# spice-usbc.net
KiCad netlist of a schematic drawn in EAGLE
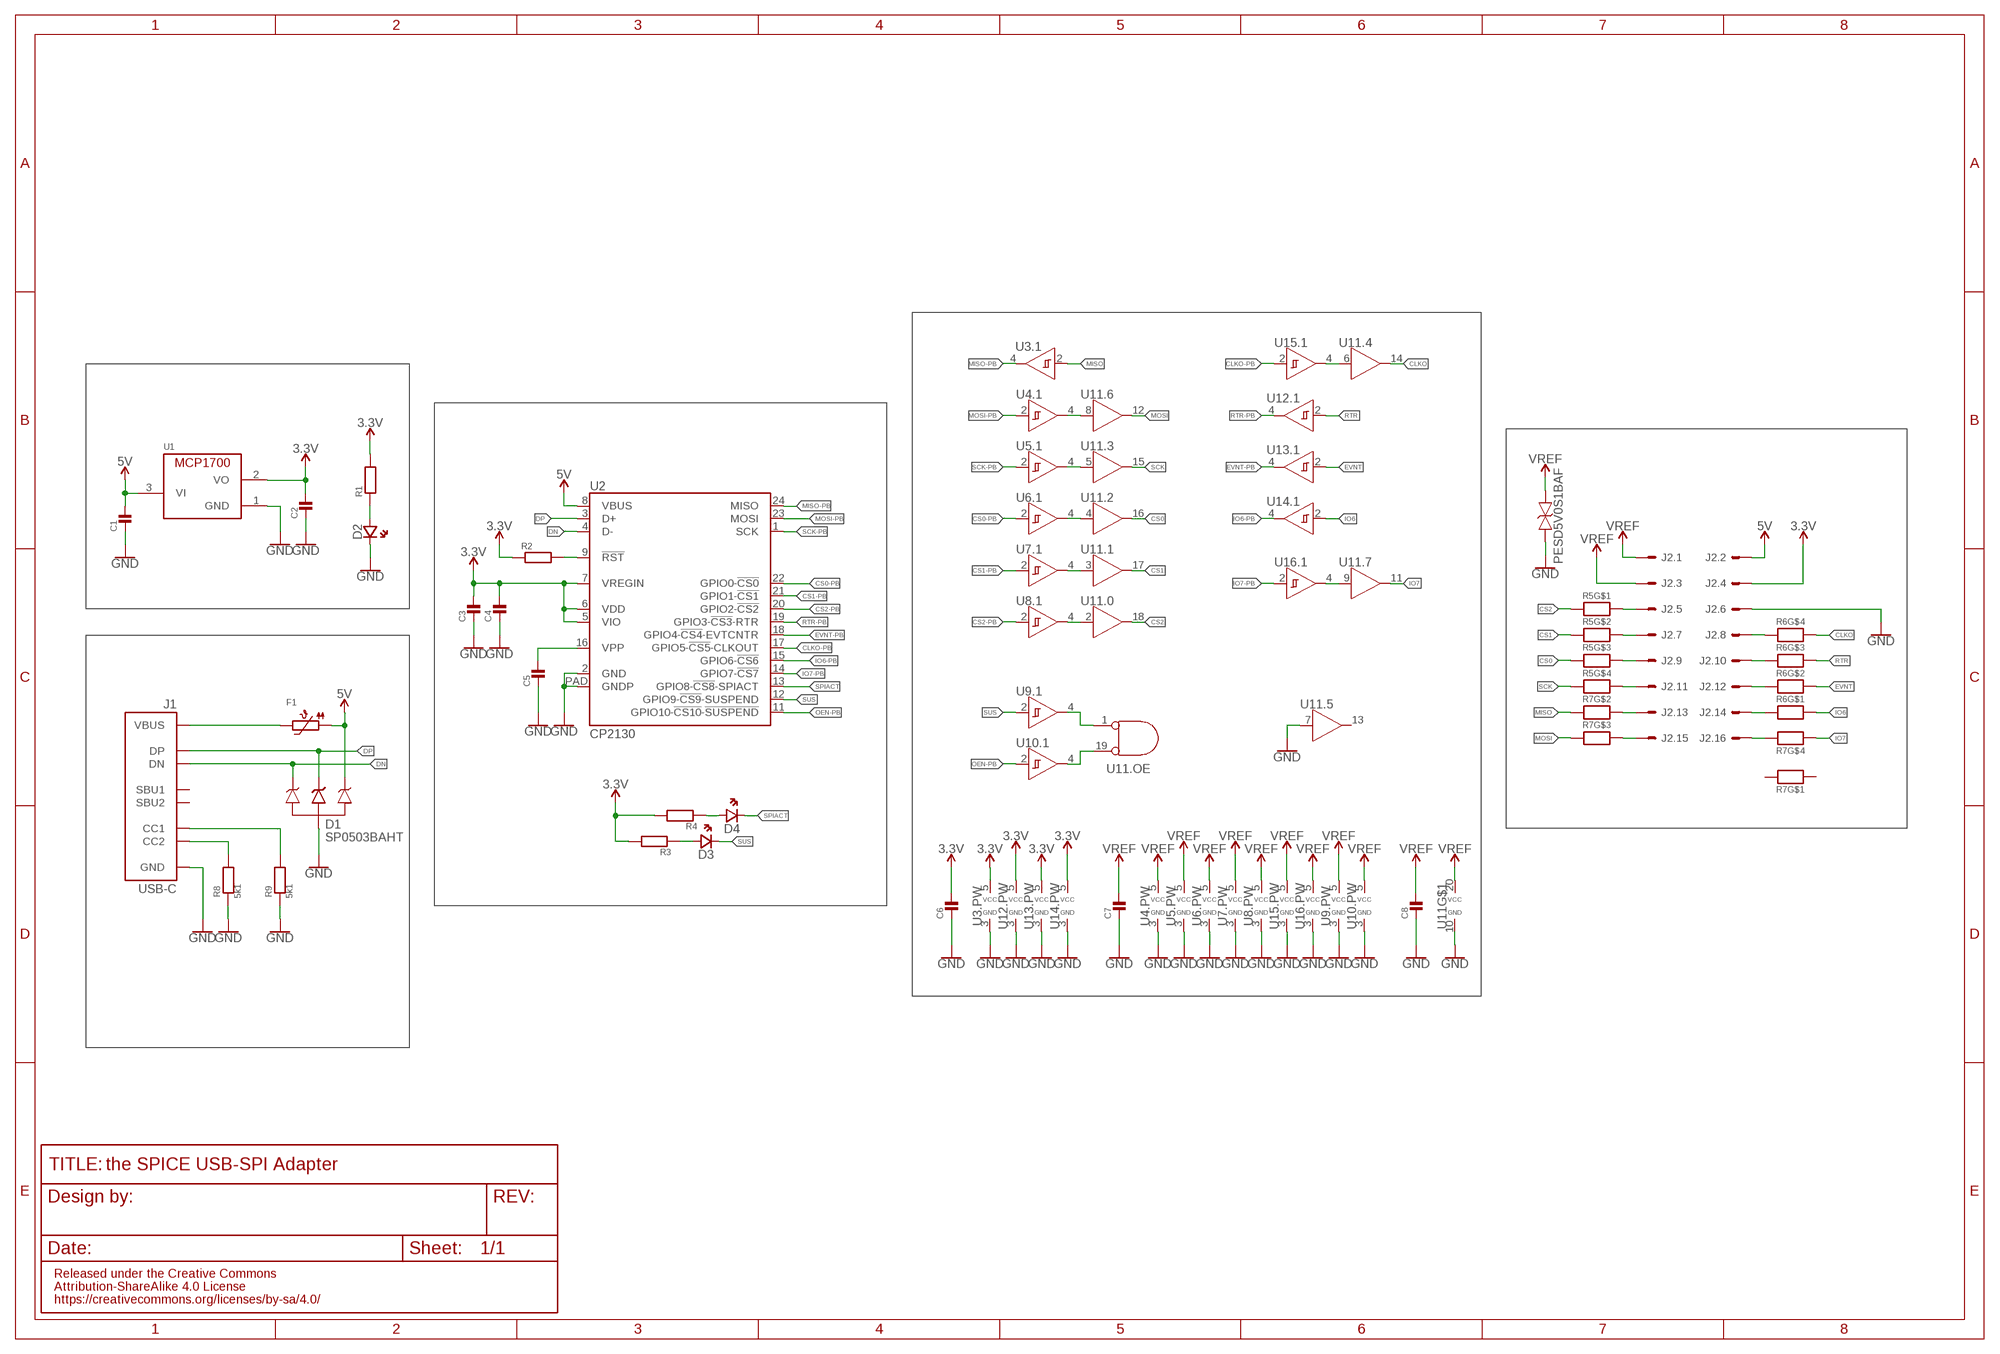
[diagram p0: schematic, sheet 1]

(export (version "E")
  (design (tool "Eeschema 10.0.6"))
  (components
    (comp (ref "C1")
      (value "MLCC0603")
      (footprint "eagle-import:0603_WAVE")
      (libsource (lib "eagle-import") (part "MLCC0603"))
    )
    (comp (ref "C2")
      (value "MLCC0603")
      (footprint "eagle-import:0603_WAVE")
      (libsource (lib "eagle-import") (part "MLCC0603"))
    )
    (comp (ref "C3")
      (value "MLCC0603")
      (footprint "eagle-import:0603_WAVE")
      (libsource (lib "eagle-import") (part "MLCC0603"))
    )
    (comp (ref "C4")
      (value "MLCC0603")
      (footprint "eagle-import:0603_WAVE")
      (libsource (lib "eagle-import") (part "MLCC0603"))
    )
    (comp (ref "C5")
      (value "MLCC0603")
      (footprint "eagle-import:0603_WAVE")
      (libsource (lib "eagle-import") (part "MLCC0603"))
    )
    (comp (ref "C6")
      (value "MLCC0603")
      (footprint "eagle-import:0603_WAVE")
      (libsource (lib "eagle-import") (part "MLCC0603"))
    )
    (comp (ref "C7")
      (value "MLCC0603")
      (footprint "eagle-import:0603_WAVE")
      (libsource (lib "eagle-import") (part "MLCC0603"))
    )
    (comp (ref "C8")
      (value "MLCC0603")
      (footprint "eagle-import:0603_WAVE")
      (libsource (lib "eagle-import") (part "MLCC0603"))
    )
    (comp (ref "D1")
      (value "SP0503BAHT")
      (footprint "eagle-import:SOT143")
      (libsource (lib "eagle-import") (part "SP0503BAHT"))
    )
    (comp (ref "D2")
      (value "LED0603")
      (footprint "eagle-import:CHIPLED_0603")
      (libsource (lib "eagle-import") (part "LED0603"))
    )
    (comp (ref "D3")
      (value "LED0603")
      (footprint "eagle-import:CHIPLED_0603")
      (libsource (lib "eagle-import") (part "LED0603"))
    )
    (comp (ref "D4")
      (value "LED0603")
      (footprint "eagle-import:CHIPLED_0603")
      (libsource (lib "eagle-import") (part "LED0603"))
    )
    (comp (ref "D5")
      (value "PESD5V0S1BAF")
      (footprint "eagle-import:SOD323")
      (libsource (lib "eagle-import") (part "PESD5V0S1BAF"))
    )
    (comp (ref "F1")
      (value "PTC1210")
      (footprint "eagle-import:PTC1210")
      (libsource (lib "eagle-import") (part "PTC1210"))
    )
    (comp (ref "J1")
      (value "USB-C")
      (footprint "eagle-import:USB-C")
      (libsource (lib "eagle-import") (part "USB-C"))
    )
    (comp (ref "J2")
      (value "2X8")
      (footprint "eagle-import:2X8_2.54")
      (libsource (lib "eagle-import") (part "2X8"))
    )
    (comp (ref "R1")
      (value "RESISTOR0603")
      (footprint "eagle-import:0603_WAVE")
      (libsource (lib "eagle-import") (part "RESISTOR0603"))
    )
    (comp (ref "R2")
      (value "RESISTOR0603")
      (footprint "eagle-import:0603_WAVE")
      (libsource (lib "eagle-import") (part "RESISTOR0603"))
    )
    (comp (ref "R3")
      (value "RESISTOR0603")
      (footprint "eagle-import:0603_WAVE")
      (libsource (lib "eagle-import") (part "RESISTOR0603"))
    )
    (comp (ref "R4")
      (value "RESISTOR0603")
      (footprint "eagle-import:0603_WAVE")
      (libsource (lib "eagle-import") (part "RESISTOR0603"))
    )
    (comp (ref "R5")
      (value "RESISTOR_4PACK")
      (footprint "eagle-import:RESPACK_4X0603")
      (libsource (lib "eagle-import") (part "RESISTOR_4PACK"))
    )
    (comp (ref "R6")
      (value "RESISTOR_4PACK")
      (footprint "eagle-import:RESPACK_4X0603")
      (libsource (lib "eagle-import") (part "RESISTOR_4PACK"))
    )
    (comp (ref "R7")
      (value "RESISTOR_4PACK")
      (footprint "eagle-import:RESPACK_4X0603")
      (libsource (lib "eagle-import") (part "RESISTOR_4PACK"))
    )
    (comp (ref "R8")
      (value "5k1")
      (footprint "eagle-import:0603_WAVE")
      (libsource (lib "eagle-import") (part "RESISTOR0603"))
    )
    (comp (ref "R9")
      (value "5k1")
      (footprint "eagle-import:0603_WAVE")
      (libsource (lib "eagle-import") (part "RESISTOR0603"))
    )
    (comp (ref "U1")
      (value "MCP1700T-3302TT")
      (footprint "eagle-import:SOT-23")
      (libsource (lib "eagle-import") (part "MCP1700T-3302TT"))
    )
    (comp (ref "U2")
      (value "CP2130")
      (footprint "eagle-import:QFN24")
      (libsource (lib "eagle-import") (part "CP2130"))
    )
    (comp (ref "U3")
      (value "74LVC1G17")
      (footprint "eagle-import:SC70-5")
      (libsource (lib "eagle-import") (part "74LVC1G17"))
    )
    (comp (ref "U4")
      (value "74LVC1G17")
      (footprint "eagle-import:SC70-5")
      (libsource (lib "eagle-import") (part "74LVC1G17"))
    )
    (comp (ref "U5")
      (value "74LVC1G17")
      (footprint "eagle-import:SC70-5")
      (libsource (lib "eagle-import") (part "74LVC1G17"))
    )
    (comp (ref "U6")
      (value "74LVC1G17")
      (footprint "eagle-import:SC70-5")
      (libsource (lib "eagle-import") (part "74LVC1G17"))
    )
    (comp (ref "U7")
      (value "74LVC1G17")
      (footprint "eagle-import:SC70-5")
      (libsource (lib "eagle-import") (part "74LVC1G17"))
    )
    (comp (ref "U8")
      (value "74LVC1G17")
      (footprint "eagle-import:SC70-5")
      (libsource (lib "eagle-import") (part "74LVC1G17"))
    )
    (comp (ref "U9")
      (value "74LVC1G17")
      (footprint "eagle-import:SC70-5")
      (libsource (lib "eagle-import") (part "74LVC1G17"))
    )
    (comp (ref "U10")
      (value "74LVC1G17")
      (footprint "eagle-import:SC70-5")
      (libsource (lib "eagle-import") (part "74LVC1G17"))
    )
    (comp (ref "U11")
      (value "74HC541")
      (footprint "eagle-import:TSSOP20")
      (libsource (lib "eagle-import") (part "74HC541"))
    )
    (comp (ref "U12")
      (value "74LVC1G17")
      (footprint "eagle-import:SC70-5")
      (libsource (lib "eagle-import") (part "74LVC1G17"))
    )
    (comp (ref "U13")
      (value "74LVC1G17")
      (footprint "eagle-import:SC70-5")
      (libsource (lib "eagle-import") (part "74LVC1G17"))
    )
    (comp (ref "U14")
      (value "74LVC1G17")
      (footprint "eagle-import:SC70-5")
      (libsource (lib "eagle-import") (part "74LVC1G17"))
    )
    (comp (ref "U15")
      (value "74LVC1G17")
      (footprint "eagle-import:SC70-5")
      (libsource (lib "eagle-import") (part "74LVC1G17"))
    )
    (comp (ref "U16")
      (value "74LVC1G17")
      (footprint "eagle-import:SC70-5")
      (libsource (lib "eagle-import") (part "74LVC1G17"))
    )
  )
  (nets
    (net (code "1") (name "3.3V") (class "Default")
      (node (ref "C2") (pin "P$1") (pinfunction "P$1_P$1") (pintype "bidirectional"))
      (node (ref "C3") (pin "P$1") (pinfunction "P$1_P$1") (pintype "bidirectional"))
      (node (ref "C4") (pin "P$1") (pinfunction "P$1_P$1") (pintype "bidirectional"))
      (node (ref "C6") (pin "P$1") (pinfunction "P$1_P$1") (pintype "bidirectional"))
      (node (ref "J2") (pin "4") (pinfunction "S_4") (pintype "passive"))
      (node (ref "R1") (pin "P$2") (pinfunction "P$2_P$2") (pintype "bidirectional"))
      (node (ref "R2") (pin "P$1") (pinfunction "P$1_P$1") (pintype "bidirectional"))
      (node (ref "R3") (pin "P$2") (pinfunction "P$2_P$2") (pintype "bidirectional"))
      (node (ref "R4") (pin "P$2") (pinfunction "P$2_P$2") (pintype "bidirectional"))
      (node (ref "U1") (pin "2") (pinfunction "VO_2") (pintype "bidirectional"))
      (node (ref "U12") (pin "5") (pinfunction "VCC_5") (pintype "bidirectional"))
      (node (ref "U13") (pin "5") (pinfunction "VCC_5") (pintype "bidirectional"))
      (node (ref "U14") (pin "5") (pinfunction "VCC_5") (pintype "bidirectional"))
      (node (ref "U2") (pin "5") (pinfunction "VIO_5") (pintype "bidirectional"))
      (node (ref "U2") (pin "6") (pinfunction "VDD_6") (pintype "bidirectional"))
      (node (ref "U2") (pin "7") (pinfunction "VREGIN_7") (pintype "bidirectional"))
      (node (ref "U3") (pin "5") (pinfunction "VCC_5") (pintype "bidirectional"))
    )
    (net (code "2") (name "5V") (class "Default")
      (node (ref "C1") (pin "P$1") (pinfunction "P$1_P$1") (pintype "bidirectional"))
      (node (ref "D1") (pin "4") (pinfunction "4_4") (pintype "bidirectional"))
      (node (ref "F1") (pin "P$1") (pinfunction "1_P$1") (pintype "passive"))
      (node (ref "J2") (pin "2") (pinfunction "S_2") (pintype "passive"))
      (node (ref "U1") (pin "3") (pinfunction "VI_3") (pintype "bidirectional"))
      (node (ref "U2") (pin "8") (pinfunction "VBUS_8") (pintype "bidirectional"))
    )
    (net (code "3") (name "CLKO") (class "Default")
      (node (ref "R6") (pin "5") (pinfunction "2_5") (pintype "passive"))
      (node (ref "U11") (pin "14") (pinfunction "Y_14") (pintype "output"))
    )
    (net (code "4") (name "CLKO-PB") (class "Default")
      (node (ref "U15") (pin "2") (pinfunction "A_2") (pintype "input"))
      (node (ref "U2") (pin "17") (pinfunction "GPIO5-~{CS5}-CLKOUT_17") (pintype "bidirectional"))
    )
    (net (code "5") (name "CS0") (class "Default")
      (node (ref "R5") (pin "3") (pinfunction "1_3") (pintype "passive"))
      (node (ref "U11") (pin "16") (pinfunction "Y_16") (pintype "output"))
    )
    (net (code "6") (name "CS0-PB") (class "Default")
      (node (ref "U2") (pin "22") (pinfunction "GPIO0-~{CS0}_22") (pintype "bidirectional"))
      (node (ref "U6") (pin "2") (pinfunction "A_2") (pintype "input"))
    )
    (net (code "7") (name "CS1") (class "Default")
      (node (ref "R5") (pin "2") (pinfunction "1_2") (pintype "passive"))
      (node (ref "U11") (pin "17") (pinfunction "Y_17") (pintype "output"))
    )
    (net (code "8") (name "CS1-PB") (class "Default")
      (node (ref "U2") (pin "21") (pinfunction "GPIO1-~{CS1}_21") (pintype "bidirectional"))
      (node (ref "U7") (pin "2") (pinfunction "A_2") (pintype "input"))
    )
    (net (code "9") (name "CS2") (class "Default")
      (node (ref "R5") (pin "1") (pinfunction "1_1") (pintype "passive"))
      (node (ref "U11") (pin "18") (pinfunction "Y_18") (pintype "output"))
    )
    (net (code "10") (name "CS2-PB") (class "Default")
      (node (ref "U2") (pin "20") (pinfunction "GPIO2-~{CS2}_20") (pintype "bidirectional"))
      (node (ref "U8") (pin "2") (pinfunction "A_2") (pintype "input"))
    )
    (net (code "11") (name "DN") (class "Default")
      (node (ref "D1") (pin "2") (pinfunction "2_2") (pintype "bidirectional"))
      (node (ref "J1") (pin "A7") (pinfunction "DN_A7") (pintype "bidirectional"))
      (node (ref "J1") (pin "B7") (pinfunction "DN_B7") (pintype "bidirectional"))
      (node (ref "U2") (pin "4") (pinfunction "D-_4") (pintype "bidirectional"))
    )
    (net (code "12") (name "DP") (class "Default")
      (node (ref "D1") (pin "3") (pinfunction "3_3") (pintype "bidirectional"))
      (node (ref "J1") (pin "A6") (pinfunction "DP_A6") (pintype "bidirectional"))
      (node (ref "J1") (pin "B6") (pinfunction "DP_B6") (pintype "bidirectional"))
      (node (ref "U2") (pin "3") (pinfunction "D+_3") (pintype "bidirectional"))
    )
    (net (code "13") (name "EVNT") (class "Default")
      (node (ref "R6") (pin "7") (pinfunction "2_7") (pintype "passive"))
      (node (ref "U13") (pin "2") (pinfunction "A_2") (pintype "input"))
    )
    (net (code "14") (name "EVNT-PB") (class "Default")
      (node (ref "U13") (pin "4") (pinfunction "Y_4") (pintype "output"))
      (node (ref "U2") (pin "18") (pinfunction "GPIO4-~{CS4}-EVTCNTR_18") (pintype "bidirectional"))
    )
    (net (code "15") (name "GND") (class "Default")
      (node (ref "C1") (pin "P$2") (pinfunction "P$2_P$2") (pintype "bidirectional"))
      (node (ref "C2") (pin "P$2") (pinfunction "P$2_P$2") (pintype "bidirectional"))
      (node (ref "C3") (pin "P$2") (pinfunction "P$2_P$2") (pintype "bidirectional"))
      (node (ref "C4") (pin "P$2") (pinfunction "P$2_P$2") (pintype "bidirectional"))
      (node (ref "C5") (pin "P$2") (pinfunction "P$2_P$2") (pintype "bidirectional"))
      (node (ref "C6") (pin "P$2") (pinfunction "P$2_P$2") (pintype "bidirectional"))
      (node (ref "C7") (pin "P$2") (pinfunction "P$2_P$2") (pintype "bidirectional"))
      (node (ref "C8") (pin "P$2") (pinfunction "P$2_P$2") (pintype "bidirectional"))
      (node (ref "D1") (pin "1") (pinfunction "1_1") (pintype "bidirectional"))
      (node (ref "D2") (pin "C") (pinfunction "CA_C") (pintype "bidirectional"))
      (node (ref "D5") (pin "P$2") (pinfunction "P$2_P$2") (pintype "bidirectional"))
      (node (ref "J1") (pin "A1_B12") (pinfunction "GND_A1_B12") (pintype "bidirectional"))
      (node (ref "J1") (pin "B1_A12") (pinfunction "GND_B1_A12") (pintype "bidirectional"))
      (node (ref "J1") (pin "SHIELD0") (pinfunction "GND_SHIELD0") (pintype "bidirectional"))
      (node (ref "J1") (pin "SHIELD1") (pinfunction "GND_SHIELD1") (pintype "bidirectional"))
      (node (ref "J1") (pin "SHIELD2") (pinfunction "GND_SHIELD2") (pintype "bidirectional"))
      (node (ref "J1") (pin "SHIELD3") (pinfunction "GND_SHIELD3") (pintype "bidirectional"))
      (node (ref "J2") (pin "6") (pinfunction "S_6") (pintype "passive"))
      (node (ref "R8") (pin "P$1") (pinfunction "P$1_P$1") (pintype "bidirectional"))
      (node (ref "R9") (pin "P$1") (pinfunction "P$1_P$1") (pintype "bidirectional"))
      (node (ref "U1") (pin "1") (pinfunction "GND_1") (pintype "bidirectional"))
      (node (ref "U10") (pin "3") (pinfunction "GND_3") (pintype "bidirectional"))
      (node (ref "U11") (pin "10") (pinfunction "GND_10") (pintype "bidirectional"))
      (node (ref "U11") (pin "7") (pinfunction "A_7") (pintype "input"))
      (node (ref "U12") (pin "3") (pinfunction "GND_3") (pintype "bidirectional"))
      (node (ref "U13") (pin "3") (pinfunction "GND_3") (pintype "bidirectional"))
      (node (ref "U14") (pin "3") (pinfunction "GND_3") (pintype "bidirectional"))
      (node (ref "U15") (pin "3") (pinfunction "GND_3") (pintype "bidirectional"))
      (node (ref "U16") (pin "3") (pinfunction "GND_3") (pintype "bidirectional"))
      (node (ref "U2") (pin "2") (pinfunction "GND_2") (pintype "bidirectional"))
      (node (ref "U2") (pin "PAD") (pinfunction "GNDP_PAD") (pintype "bidirectional"))
      (node (ref "U3") (pin "3") (pinfunction "GND_3") (pintype "bidirectional"))
      (node (ref "U4") (pin "3") (pinfunction "GND_3") (pintype "bidirectional"))
      (node (ref "U5") (pin "3") (pinfunction "GND_3") (pintype "bidirectional"))
      (node (ref "U6") (pin "3") (pinfunction "GND_3") (pintype "bidirectional"))
      (node (ref "U7") (pin "3") (pinfunction "GND_3") (pintype "bidirectional"))
      (node (ref "U8") (pin "3") (pinfunction "GND_3") (pintype "bidirectional"))
      (node (ref "U9") (pin "3") (pinfunction "GND_3") (pintype "bidirectional"))
    )
    (net (code "16") (name "IO6") (class "Default")
      (node (ref "R6") (pin "8") (pinfunction "2_8") (pintype "passive"))
      (node (ref "U14") (pin "2") (pinfunction "A_2") (pintype "input"))
    )
    (net (code "17") (name "IO6-PB") (class "Default")
      (node (ref "U14") (pin "4") (pinfunction "Y_4") (pintype "output"))
      (node (ref "U2") (pin "15") (pinfunction "GPIO6-~{CS6}_15") (pintype "bidirectional"))
    )
    (net (code "18") (name "IO7") (class "Default")
      (node (ref "R7") (pin "4") (pinfunction "1_4") (pintype "passive"))
      (node (ref "U11") (pin "11") (pinfunction "Y_11") (pintype "output"))
    )
    (net (code "19") (name "IO7-PB") (class "Default")
      (node (ref "U16") (pin "2") (pinfunction "A_2") (pintype "input"))
      (node (ref "U2") (pin "14") (pinfunction "GPIO7-~{CS7}_14") (pintype "bidirectional"))
    )
    (net (code "20") (name "MISO") (class "Default")
      (node (ref "R7") (pin "2") (pinfunction "1_2") (pintype "passive"))
      (node (ref "U3") (pin "2") (pinfunction "A_2") (pintype "input"))
    )
    (net (code "21") (name "MISO-PB") (class "Default")
      (node (ref "U2") (pin "24") (pinfunction "MISO_24") (pintype "bidirectional"))
      (node (ref "U3") (pin "4") (pinfunction "Y_4") (pintype "output"))
    )
    (net (code "22") (name "MOSI") (class "Default")
      (node (ref "R7") (pin "3") (pinfunction "1_3") (pintype "passive"))
      (node (ref "U11") (pin "12") (pinfunction "Y_12") (pintype "output"))
    )
    (net (code "23") (name "MOSI-PB") (class "Default")
      (node (ref "U2") (pin "23") (pinfunction "MOSI_23") (pintype "bidirectional"))
      (node (ref "U4") (pin "2") (pinfunction "A_2") (pintype "input"))
    )
    (net (code "24") (name "Net-(D2-AN)") (class "Default")
      (node (ref "D2") (pin "A") (pinfunction "AN_A") (pintype "bidirectional"))
      (node (ref "R1") (pin "P$1") (pinfunction "P$1_P$1") (pintype "bidirectional"))
    )
    (net (code "25") (name "Net-(D3-AN)") (class "Default")
      (node (ref "D3") (pin "A") (pinfunction "AN_A") (pintype "bidirectional"))
      (node (ref "R3") (pin "P$1") (pinfunction "P$1_P$1") (pintype "bidirectional"))
    )
    (net (code "26") (name "Net-(D4-AN)") (class "Default")
      (node (ref "D4") (pin "A") (pinfunction "AN_A") (pintype "bidirectional"))
      (node (ref "R4") (pin "P$1") (pinfunction "P$1_P$1") (pintype "bidirectional"))
    )
    (net (code "27") (name "Net-(F1-2)") (class "Default")
      (node (ref "F1") (pin "P$2") (pinfunction "2_P$2") (pintype "passive"))
      (node (ref "J1") (pin "A4_B9") (pinfunction "VBUS_A4_B9") (pintype "bidirectional"))
      (node (ref "J1") (pin "B4_A9") (pinfunction "VBUS_B4_A9") (pintype "bidirectional"))
    )
    (net (code "28") (name "Net-(J1-CC1)") (class "Default")
      (node (ref "J1") (pin "A5") (pinfunction "CC1_A5") (pintype "bidirectional"))
      (node (ref "R9") (pin "P$2") (pinfunction "P$2_P$2") (pintype "bidirectional"))
    )
    (net (code "29") (name "Net-(J1-CC2)") (class "Default")
      (node (ref "J1") (pin "B5") (pinfunction "CC2_B5") (pintype "bidirectional"))
      (node (ref "R8") (pin "P$2") (pinfunction "P$2_P$2") (pintype "bidirectional"))
    )
    (net (code "30") (name "Net-(J2B-S)") (class "Default")
      (node (ref "J2") (pin "10") (pinfunction "S_10") (pintype "passive"))
      (node (ref "R6") (pin "3") (pinfunction "1_3") (pintype "passive"))
    )
    (net (code "31") (name "Net-(J2C-S)") (class "Default")
      (node (ref "J2") (pin "11") (pinfunction "S_11") (pintype "passive"))
      (node (ref "R5") (pin "5") (pinfunction "2_5") (pintype "passive"))
    )
    (net (code "32") (name "Net-(J2D-S)") (class "Default")
      (node (ref "J2") (pin "12") (pinfunction "S_12") (pintype "passive"))
      (node (ref "R6") (pin "2") (pinfunction "1_2") (pintype "passive"))
    )
    (net (code "33") (name "Net-(J2E-S)") (class "Default")
      (node (ref "J2") (pin "13") (pinfunction "S_13") (pintype "passive"))
      (node (ref "R7") (pin "7") (pinfunction "2_7") (pintype "passive"))
    )
    (net (code "34") (name "Net-(J2F-S)") (class "Default")
      (node (ref "J2") (pin "14") (pinfunction "S_14") (pintype "passive"))
      (node (ref "R6") (pin "1") (pinfunction "1_1") (pintype "passive"))
    )
    (net (code "35") (name "Net-(J2G-S)") (class "Default")
      (node (ref "J2") (pin "15") (pinfunction "S_15") (pintype "passive"))
      (node (ref "R7") (pin "6") (pinfunction "2_6") (pintype "passive"))
    )
    (net (code "36") (name "Net-(J2H-S)") (class "Default")
      (node (ref "J2") (pin "16") (pinfunction "S_16") (pintype "passive"))
      (node (ref "R7") (pin "5") (pinfunction "2_5") (pintype "passive"))
    )
    (net (code "37") (name "Net-(J2L-S)") (class "Default")
      (node (ref "J2") (pin "5") (pinfunction "S_5") (pintype "passive"))
      (node (ref "R5") (pin "8") (pinfunction "2_8") (pintype "passive"))
    )
    (net (code "38") (name "Net-(J2N-S)") (class "Default")
      (node (ref "J2") (pin "7") (pinfunction "S_7") (pintype "passive"))
      (node (ref "R5") (pin "7") (pinfunction "2_7") (pintype "passive"))
    )
    (net (code "39") (name "Net-(J2O-S)") (class "Default")
      (node (ref "J2") (pin "8") (pinfunction "S_8") (pintype "passive"))
      (node (ref "R6") (pin "4") (pinfunction "1_4") (pintype "passive"))
    )
    (net (code "40") (name "Net-(J2P-S)") (class "Default")
      (node (ref "J2") (pin "9") (pinfunction "S_9") (pintype "passive"))
      (node (ref "R5") (pin "6") (pinfunction "2_6") (pintype "passive"))
    )
    (net (code "41") (name "Net-(U2-VPP)") (class "Default")
      (node (ref "C5") (pin "P$1") (pinfunction "P$1_P$1") (pintype "bidirectional"))
      (node (ref "U2") (pin "16") (pinfunction "VPP_16") (pintype "bidirectional"))
    )
    (net (code "42") (name "Net-(U2-~{RST})") (class "Default")
      (node (ref "R2") (pin "P$2") (pinfunction "P$2_P$2") (pintype "bidirectional"))
      (node (ref "U2") (pin "9") (pinfunction "~{RST}_9") (pintype "bidirectional"))
    )
    (net (code "43") (name "Net-(U10A-Y)") (class "Default")
      (node (ref "U10") (pin "4") (pinfunction "Y_4") (pintype "output"))
      (node (ref "U11") (pin "19") (pinfunction "B_19") (pintype "input"))
    )
    (net (code "44") (name "Net-(U11A-A)") (class "Default")
      (node (ref "U11") (pin "2") (pinfunction "A_2") (pintype "input"))
      (node (ref "U8") (pin "4") (pinfunction "Y_4") (pintype "output"))
    )
    (net (code "45") (name "Net-(U11B-A)") (class "Default")
      (node (ref "U11") (pin "3") (pinfunction "A_3") (pintype "input"))
      (node (ref "U7") (pin "4") (pinfunction "Y_4") (pintype "output"))
    )
    (net (code "46") (name "Net-(U11C-A)") (class "Default")
      (node (ref "U11") (pin "4") (pinfunction "A_4") (pintype "input"))
      (node (ref "U6") (pin "4") (pinfunction "Y_4") (pintype "output"))
    )
    (net (code "47") (name "Net-(U11D-A)") (class "Default")
      (node (ref "U11") (pin "5") (pinfunction "A_5") (pintype "input"))
      (node (ref "U5") (pin "4") (pinfunction "Y_4") (pintype "output"))
    )
    (net (code "48") (name "Net-(U11E-A)") (class "Default")
      (node (ref "U11") (pin "6") (pinfunction "A_6") (pintype "input"))
      (node (ref "U15") (pin "4") (pinfunction "Y_4") (pintype "output"))
    )
    (net (code "49") (name "Net-(U11G-A)") (class "Default")
      (node (ref "U11") (pin "8") (pinfunction "A_8") (pintype "input"))
      (node (ref "U4") (pin "4") (pinfunction "Y_4") (pintype "output"))
    )
    (net (code "50") (name "Net-(U11H-A)") (class "Default")
      (node (ref "U11") (pin "9") (pinfunction "A_9") (pintype "input"))
      (node (ref "U16") (pin "4") (pinfunction "Y_4") (pintype "output"))
    )
    (net (code "51") (name "Net-(U11I-A)") (class "Default")
      (node (ref "U11") (pin "1") (pinfunction "A_1") (pintype "input"))
      (node (ref "U9") (pin "4") (pinfunction "Y_4") (pintype "output"))
    )
    (net (code "52") (name "OEN-PB") (class "Default")
      (node (ref "U10") (pin "2") (pinfunction "A_2") (pintype "input"))
      (node (ref "U2") (pin "11") (pinfunction "GPIO10-~{CS10}-~{SUSPEND}_11") (pintype "bidirectional"))
    )
    (net (code "53") (name "RTR") (class "Default")
      (node (ref "R6") (pin "6") (pinfunction "2_6") (pintype "passive"))
      (node (ref "U12") (pin "2") (pinfunction "A_2") (pintype "input"))
    )
    (net (code "54") (name "RTR-PB") (class "Default")
      (node (ref "U12") (pin "4") (pinfunction "Y_4") (pintype "output"))
      (node (ref "U2") (pin "19") (pinfunction "GPIO3-~{CS3}-RTR_19") (pintype "bidirectional"))
    )
    (net (code "55") (name "SCK") (class "Default")
      (node (ref "R5") (pin "4") (pinfunction "1_4") (pintype "passive"))
      (node (ref "U11") (pin "15") (pinfunction "Y_15") (pintype "output"))
    )
    (net (code "56") (name "SCK-PB") (class "Default")
      (node (ref "U2") (pin "1") (pinfunction "SCK_1") (pintype "bidirectional"))
      (node (ref "U5") (pin "2") (pinfunction "A_2") (pintype "input"))
    )
    (net (code "57") (name "SPIACT") (class "Default")
      (node (ref "D4") (pin "C") (pinfunction "CA_C") (pintype "bidirectional"))
      (node (ref "U2") (pin "13") (pinfunction "GPIO8-~{CS8}-SPIACT_13") (pintype "bidirectional"))
    )
    (net (code "58") (name "SUS") (class "Default")
      (node (ref "D3") (pin "C") (pinfunction "CA_C") (pintype "bidirectional"))
      (node (ref "U2") (pin "12") (pinfunction "GPIO9-~{CS9}-SUSPEND_12") (pintype "bidirectional"))
      (node (ref "U9") (pin "2") (pinfunction "A_2") (pintype "input"))
    )
    (net (code "59") (name "VREF") (class "Default")
      (node (ref "C7") (pin "P$1") (pinfunction "P$1_P$1") (pintype "bidirectional"))
      (node (ref "C8") (pin "P$1") (pinfunction "P$1_P$1") (pintype "bidirectional"))
      (node (ref "D5") (pin "P$1") (pinfunction "P$1_P$1") (pintype "bidirectional"))
      (node (ref "J2") (pin "1") (pinfunction "S_1") (pintype "passive"))
      (node (ref "J2") (pin "3") (pinfunction "S_3") (pintype "passive"))
      (node (ref "U10") (pin "5") (pinfunction "VCC_5") (pintype "bidirectional"))
      (node (ref "U11") (pin "20") (pinfunction "VCC_20") (pintype "bidirectional"))
      (node (ref "U15") (pin "5") (pinfunction "VCC_5") (pintype "bidirectional"))
      (node (ref "U16") (pin "5") (pinfunction "VCC_5") (pintype "bidirectional"))
      (node (ref "U4") (pin "5") (pinfunction "VCC_5") (pintype "bidirectional"))
      (node (ref "U5") (pin "5") (pinfunction "VCC_5") (pintype "bidirectional"))
      (node (ref "U6") (pin "5") (pinfunction "VCC_5") (pintype "bidirectional"))
      (node (ref "U7") (pin "5") (pinfunction "VCC_5") (pintype "bidirectional"))
      (node (ref "U8") (pin "5") (pinfunction "VCC_5") (pintype "bidirectional"))
      (node (ref "U9") (pin "5") (pinfunction "VCC_5") (pintype "bidirectional"))
    )
    (net (code "60") (name "unconnected-(J1-SBU1-PadA8)") (class "Default")
      (node (ref "J1") (pin "A8") (pinfunction "SBU1_A8") (pintype "bidirectional"))
    )
    (net (code "61") (name "unconnected-(J1-SBU2-PadB8)") (class "Default")
      (node (ref "J1") (pin "B8") (pinfunction "SBU2_B8") (pintype "bidirectional"))
    )
    (net (code "62") (name "unconnected-(R7-Pad1)") (class "Default")
      (node (ref "R7") (pin "1") (pinfunction "1_1") (pintype "passive"))
    )
    (net (code "63") (name "unconnected-(R7A-2-Pad8)") (class "Default")
      (node (ref "R7") (pin "8") (pinfunction "2_8") (pintype "passive"))
    )
    (net (code "64") (name "unconnected-(U11F-Y-Pad13)") (class "Default")
      (node (ref "U11") (pin "13") (pinfunction "Y_13") (pintype "output"))
    )
  )
)
